# tracker.net
KiCad netlist of a schematic drawn in EAGLE
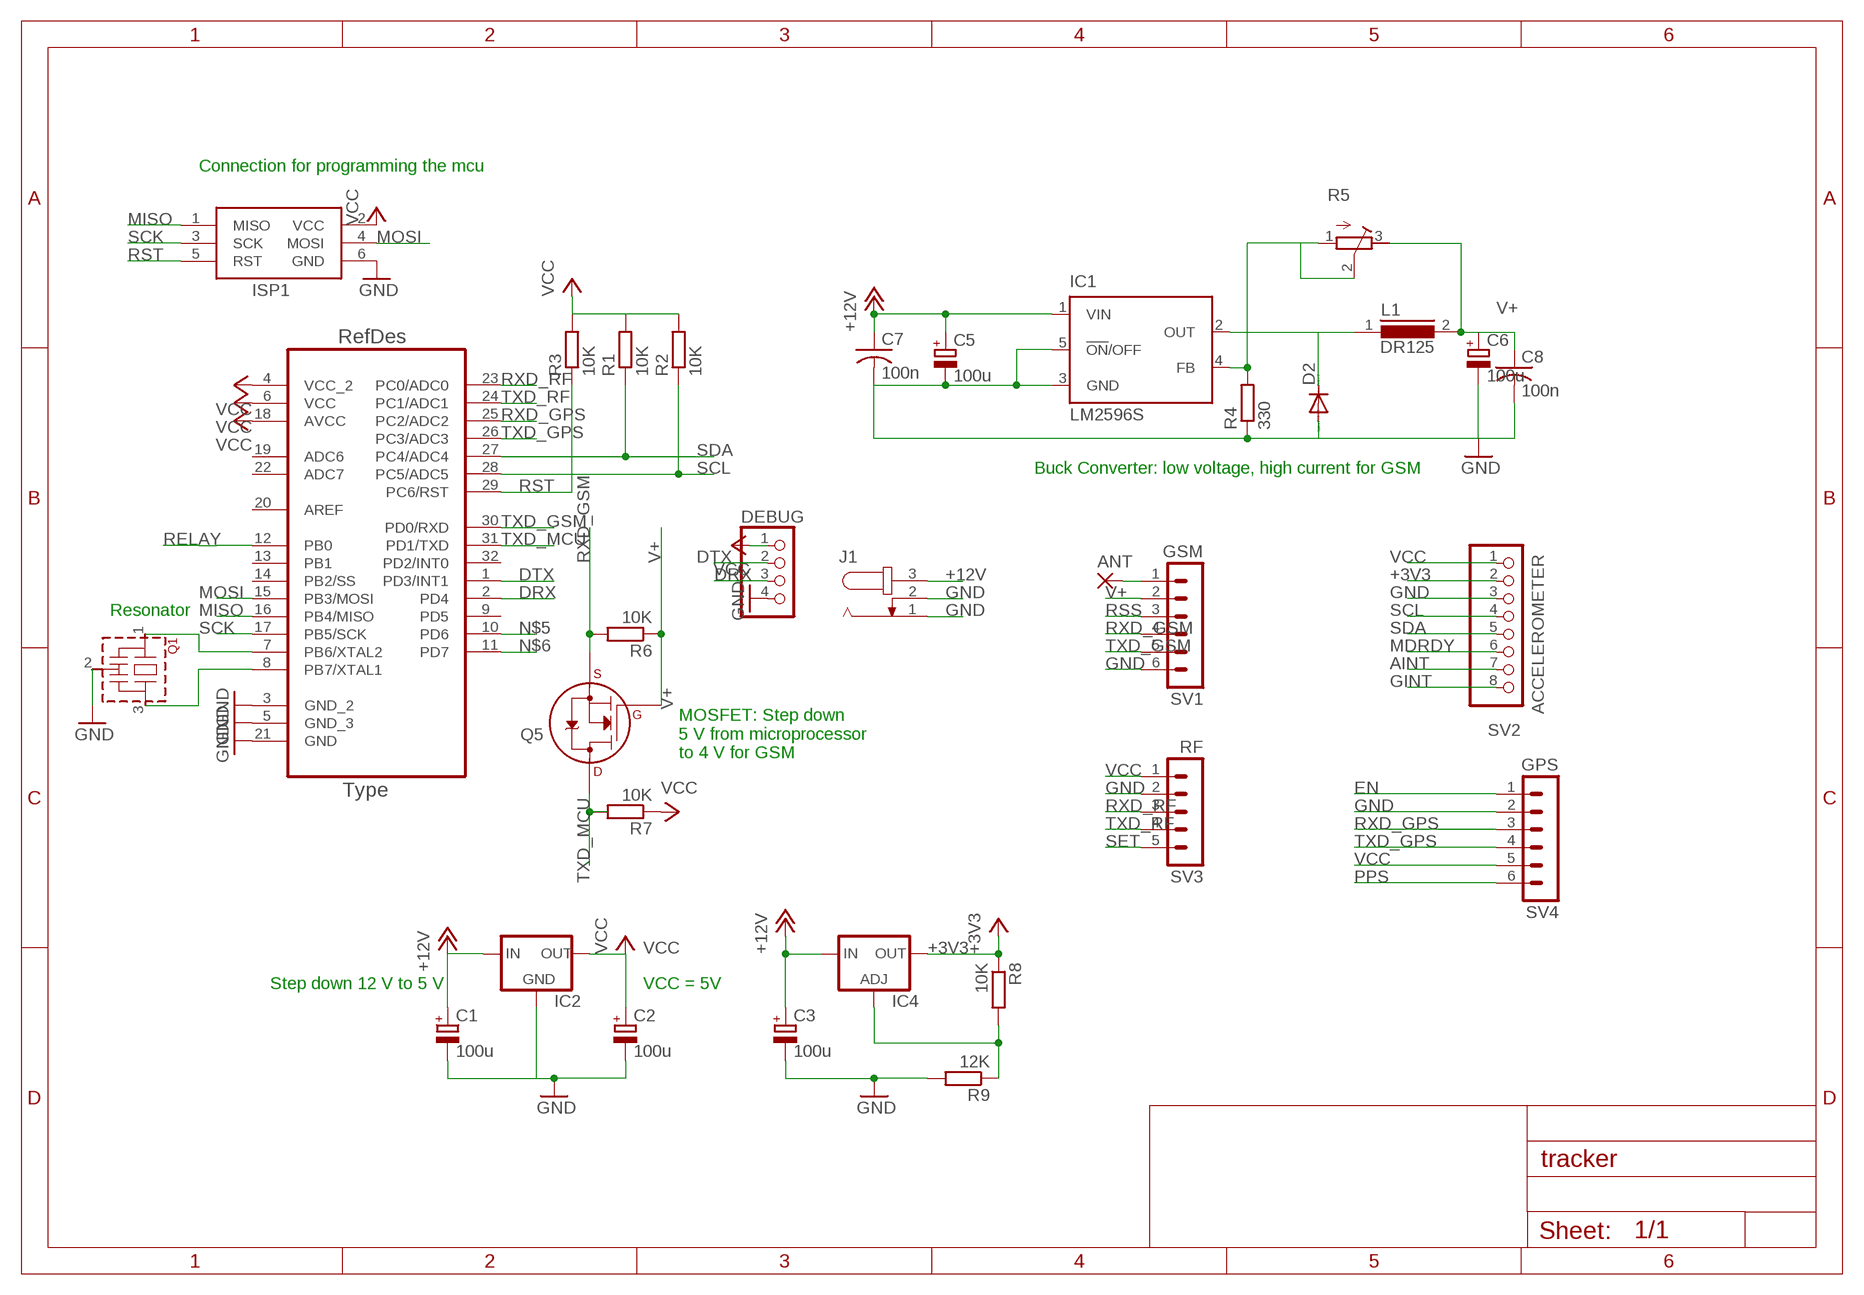
[diagram p0: schematic, sheet 1]

(export (version "E")
  (design (tool "Eeschema 10.0.6"))
  (components
    (comp (ref "ANT")
      (value "WIREPAD2,15/1,0")
      (footprint "eagle-import:2,15_1,0")
      (libsource (lib "eagle-import") (part "WIREPAD2,15/1,0"))
    )
    (comp (ref "C1")
      (value "100u")
      (footprint "eagle-import:E2,5-5")
      (libsource (lib "eagle-import") (part "CPOL-EUE2.5-5"))
    )
    (comp (ref "C2")
      (value "100u")
      (footprint "eagle-import:E2,5-5")
      (libsource (lib "eagle-import") (part "CPOL-EUE2.5-5"))
    )
    (comp (ref "C3")
      (value "100u")
      (footprint "eagle-import:E2,5-5")
      (libsource (lib "eagle-import") (part "CPOL-EUE2.5-5"))
    )
    (comp (ref "C5")
      (value "100u")
      (footprint "eagle-import:E2,5-5")
      (libsource (lib "eagle-import") (part "CPOL-EUE2.5-5"))
    )
    (comp (ref "C6")
      (value "100u")
      (footprint "eagle-import:E2,5-5")
      (libsource (lib "eagle-import") (part "CPOL-EUE2.5-5"))
    )
    (comp (ref "C7")
      (value "100n")
      (footprint "eagle-import:C025-024X044")
      (libsource (lib "eagle-import") (part "C-US025-024X044"))
    )
    (comp (ref "C8")
      (value "100n")
      (footprint "eagle-import:C025-024X044")
      (libsource (lib "eagle-import") (part "C-US025-024X044"))
    )
    (comp (ref "D2")
      (value "DIODE-DO-214AC")
      (footprint "eagle-import:DO-214AC")
      (libsource (lib "eagle-import") (part "DIODE-DO-214AC"))
    )
    (comp (ref "DEBUG")
      (value "PINHD-1X4")
      (footprint "eagle-import:1X04")
      (libsource (lib "eagle-import") (part "PINHD-1X4"))
    )
    (comp (ref "IC1")
      (value "LM2596S")
      (footprint "eagle-import:TO263-5")
      (fields (field (name "MF") "NATIONAL SEMICONDUCTOR") (field (name "MPN") "LM2596S-ADJ/NOPB"))
      (libsource (lib "eagle-import") (part "LM2596S"))
    )
    (comp (ref "IC2")
      (value "78XXS")
      (footprint "eagle-import:78XXS")
      (libsource (lib "eagle-import") (part "78XXS"))
    )
    (comp (ref "IC4")
      (value "LM317TS")
      (footprint "eagle-import:317TS")
      (libsource (lib "eagle-import") (part "LM317TS"))
    )
    (comp (ref "ISP1")
      (value "AVRISP-6")
      (footprint "eagle-import:AVRISP")
      (libsource (lib "eagle-import") (part "AVRISP-6"))
    )
    (comp (ref "J1")
      (value "JACK-PLUG0")
      (footprint "eagle-import:SPC4077")
      (libsource (lib "eagle-import") (part "JACK-PLUG0"))
    )
    (comp (ref "L1")
      (value "DR125")
      (footprint "eagle-import:DR125")
      (libsource (lib "eagle-import") (part "DR125"))
    )
    (comp (ref "Q1")
      (value "CSTLS_X")
      (footprint "eagle-import:CSTLS_X")
      (libsource (lib "eagle-import") (part "CSTLS_X"))
    )
    (comp (ref "Q5")
      (value "2N7000_TO92")
      (footprint "eagle-import:TO-92")
      (libsource (lib "eagle-import") (part "2N700_TO920"))
    )
    (comp (ref "R1")
      (value "10K")
      (footprint "eagle-import:R1210")
      (libsource (lib "eagle-import") (part "R-EU_R1210"))
    )
    (comp (ref "R2")
      (value "10K")
      (footprint "eagle-import:R1210")
      (libsource (lib "eagle-import") (part "R-EU_R1210"))
    )
    (comp (ref "R3")
      (value "10K")
      (footprint "eagle-import:R1210")
      (libsource (lib "eagle-import") (part "R-EU_R1210"))
    )
    (comp (ref "R4")
      (value "330")
      (footprint "eagle-import:R1210")
      (libsource (lib "eagle-import") (part "R-EU_R1210"))
    )
    (comp (ref "R5")
      (value "R-TRIMM64X")
      (footprint "eagle-import:RTRIM64X")
      (libsource (lib "eagle-import") (part "R-TRIMM64X"))
    )
    (comp (ref "R6")
      (value "10K")
      (footprint "eagle-import:R1210")
      (libsource (lib "eagle-import") (part "R-EU_R1210"))
    )
    (comp (ref "R7")
      (value "10K")
      (footprint "eagle-import:R1210")
      (libsource (lib "eagle-import") (part "R-EU_R1210"))
    )
    (comp (ref "R8")
      (value "10K")
      (footprint "eagle-import:0207_10")
      (libsource (lib "eagle-import") (part "resistor_348_R-EU_0207/10"))
    )
    (comp (ref "R9")
      (value "12K")
      (footprint "eagle-import:0207_10")
      (libsource (lib "eagle-import") (part "R-EU_0207/10"))
    )
    (comp (ref "SV1")
      (value "GSM")
      (footprint "eagle-import:MA06-1")
      (libsource (lib "eagle-import") (part "MA06-1"))
    )
    (comp (ref "SV2")
      (value "ACCELEROMETER")
      (footprint "eagle-import:1X08")
      (libsource (lib "eagle-import") (part "PINHD-1X8"))
    )
    (comp (ref "SV3")
      (value "RF")
      (footprint "eagle-import:MA05-1")
      (libsource (lib "eagle-import") (part "MA05-1"))
    )
    (comp (ref "SV4")
      (value "GPS")
      (footprint "eagle-import:MA06-1")
      (libsource (lib "eagle-import") (part "MA06-1"))
    )
    (comp (ref "U1")
      (value "ATMEGA328P-AU")
      (footprint "eagle-import:QFP80P900X900X120-32N")
      (libsource (lib "eagle-import") (part "ATMEGA328P-AU"))
    )
  )
  (nets
    (net (code "1") (name "+3V3") (class "Default")
      (node (ref "IC4") (pin "2") (pinfunction "OUT_2") (pintype "passive"))
      (node (ref "R8") (pin "1") (pinfunction "1_1") (pintype "passive"))
      (node (ref "SV2") (pin "2") (pinfunction "2_2") (pintype "passive"))
    )
    (net (code "2") (name "+12V") (class "Default")
      (node (ref "C1") (pin "+") (pinfunction "+_+") (pintype "passive"))
      (node (ref "C3") (pin "+") (pinfunction "+_+") (pintype "passive"))
      (node (ref "C5") (pin "+") (pinfunction "+_+") (pintype "passive"))
      (node (ref "C7") (pin "1") (pinfunction "1_1") (pintype "passive"))
      (node (ref "IC1") (pin "1") (pinfunction "VIN_1") (pintype "input"))
      (node (ref "IC2") (pin "IN") (pinfunction "IN_IN") (pintype "input"))
      (node (ref "IC4") (pin "3") (pinfunction "IN_3") (pintype "input"))
      (node (ref "J1") (pin "3") (pinfunction "3_3") (pintype "passive"))
    )
    (net (code "3") (name "/AINT") (class "Default")
      (node (ref "SV2") (pin "7") (pinfunction "7_7") (pintype "passive"))
    )
    (net (code "4") (name "/DRX") (class "Default")
      (node (ref "DEBUG") (pin "3") (pinfunction "3_3") (pintype "passive"))
      (node (ref "U1") (pin "2") (pinfunction "PD4_2") (pintype "bidirectional"))
    )
    (net (code "5") (name "/DTX") (class "Default")
      (node (ref "DEBUG") (pin "2") (pinfunction "2_2") (pintype "passive"))
      (node (ref "U1") (pin "1") (pinfunction "PD3/INT1_1") (pintype "bidirectional"))
    )
    (net (code "6") (name "/EN") (class "Default")
      (node (ref "SV4") (pin "1") (pinfunction "1_1") (pintype "passive"))
    )
    (net (code "7") (name "/GINT") (class "Default")
      (node (ref "SV2") (pin "8") (pinfunction "8_8") (pintype "passive"))
    )
    (net (code "8") (name "/MDRDY") (class "Default")
      (node (ref "SV2") (pin "6") (pinfunction "6_6") (pintype "passive"))
    )
    (net (code "9") (name "/MISO") (class "Default")
      (node (ref "ISP1") (pin "1") (pinfunction "MISO_1") (pintype "input"))
      (node (ref "U1") (pin "16") (pinfunction "PB4/MISO_16") (pintype "bidirectional"))
    )
    (net (code "10") (name "/MOSI") (class "Default")
      (node (ref "ISP1") (pin "4") (pinfunction "MOSI_4") (pintype "output"))
      (node (ref "U1") (pin "15") (pinfunction "PB3/MOSI_15") (pintype "bidirectional"))
    )
    (net (code "11") (name "/N$5") (class "Default")
      (node (ref "U1") (pin "10") (pinfunction "PD6_10") (pintype "bidirectional"))
    )
    (net (code "12") (name "/N$6") (class "Default")
      (node (ref "U1") (pin "11") (pinfunction "PD7_11") (pintype "bidirectional"))
    )
    (net (code "13") (name "/PPS") (class "Default")
      (node (ref "SV4") (pin "6") (pinfunction "6_6") (pintype "passive"))
    )
    (net (code "14") (name "/RELAY") (class "Default")
      (node (ref "U1") (pin "12") (pinfunction "PB0_12") (pintype "bidirectional"))
    )
    (net (code "15") (name "/RSS") (class "Default")
      (node (ref "SV1") (pin "3") (pinfunction "3_3") (pintype "passive"))
    )
    (net (code "16") (name "/RST") (class "Default")
      (node (ref "ISP1") (pin "5") (pinfunction "RST_5") (pintype "output"))
      (node (ref "R3") (pin "1") (pinfunction "1_1") (pintype "passive"))
      (node (ref "U1") (pin "29") (pinfunction "PC6/RST_29") (pintype "bidirectional"))
    )
    (net (code "17") (name "/RXD_GPS") (class "Default")
      (node (ref "SV4") (pin "3") (pinfunction "3_3") (pintype "passive"))
      (node (ref "U1") (pin "25") (pinfunction "PC2/ADC2_25") (pintype "bidirectional"))
    )
    (net (code "18") (name "/RXD_GSM") (class "Default")
      (node (ref "Q5") (pin "1") (pinfunction "S_1") (pintype "bidirectional"))
      (node (ref "R6") (pin "2") (pinfunction "2_2") (pintype "passive"))
      (node (ref "SV1") (pin "4") (pinfunction "4_4") (pintype "passive"))
    )
    (net (code "19") (name "/RXD_RF") (class "Default")
      (node (ref "SV3") (pin "3") (pinfunction "3_3") (pintype "passive"))
      (node (ref "U1") (pin "23") (pinfunction "PC0/ADC0_23") (pintype "bidirectional"))
    )
    (net (code "20") (name "/SCK") (class "Default")
      (node (ref "ISP1") (pin "3") (pinfunction "SCK_3") (pintype "output"))
      (node (ref "U1") (pin "17") (pinfunction "PB5/SCK_17") (pintype "bidirectional"))
    )
    (net (code "21") (name "/SCL") (class "Default")
      (node (ref "R2") (pin "1") (pinfunction "1_1") (pintype "passive"))
      (node (ref "SV2") (pin "4") (pinfunction "4_4") (pintype "passive"))
      (node (ref "U1") (pin "28") (pinfunction "PC5/ADC5_28") (pintype "bidirectional"))
    )
    (net (code "22") (name "/SDA") (class "Default")
      (node (ref "R1") (pin "1") (pinfunction "1_1") (pintype "passive"))
      (node (ref "SV2") (pin "5") (pinfunction "5_5") (pintype "passive"))
      (node (ref "U1") (pin "27") (pinfunction "PC4/ADC4_27") (pintype "bidirectional"))
    )
    (net (code "23") (name "/SET") (class "Default")
      (node (ref "SV3") (pin "5") (pinfunction "5_5") (pintype "passive"))
    )
    (net (code "24") (name "/TXD_GPS") (class "Default")
      (node (ref "SV4") (pin "4") (pinfunction "4_4") (pintype "passive"))
      (node (ref "U1") (pin "26") (pinfunction "PC3/ADC3_26") (pintype "bidirectional"))
    )
    (net (code "25") (name "/TXD_GSM") (class "Default")
      (node (ref "SV1") (pin "5") (pinfunction "5_5") (pintype "passive"))
      (node (ref "U1") (pin "30") (pinfunction "PD0/RXD_30") (pintype "bidirectional"))
    )
    (net (code "26") (name "/TXD_MCU") (class "Default")
      (node (ref "Q5") (pin "3") (pinfunction "D_3") (pintype "bidirectional"))
      (node (ref "R7") (pin "2") (pinfunction "2_2") (pintype "passive"))
      (node (ref "U1") (pin "31") (pinfunction "PD1/TXD_31") (pintype "bidirectional"))
    )
    (net (code "27") (name "/TXD_RF") (class "Default")
      (node (ref "SV3") (pin "4") (pinfunction "4_4") (pintype "passive"))
      (node (ref "U1") (pin "24") (pinfunction "PC1/ADC1_24") (pintype "bidirectional"))
    )
    (net (code "28") (name "/V+") (class "Default")
      (node (ref "C6") (pin "+") (pinfunction "+_+") (pintype "passive"))
      (node (ref "C8") (pin "1") (pinfunction "1_1") (pintype "passive"))
      (node (ref "L1") (pin "2") (pinfunction "2_2") (pintype "passive"))
      (node (ref "Q5") (pin "2") (pinfunction "G_2") (pintype "tri_state"))
      (node (ref "R5") (pin "3") (pinfunction "E_3") (pintype "passive"))
      (node (ref "R6") (pin "1") (pinfunction "1_1") (pintype "passive"))
      (node (ref "SV1") (pin "2") (pinfunction "2_2") (pintype "passive"))
    )
    (net (code "29") (name "GND") (class "Default")
      (node (ref "C1") (pin "-") (pinfunction "-_-") (pintype "passive"))
      (node (ref "C2") (pin "-") (pinfunction "-_-") (pintype "passive"))
      (node (ref "C3") (pin "-") (pinfunction "-_-") (pintype "passive"))
      (node (ref "C5") (pin "-") (pinfunction "-_-") (pintype "passive"))
      (node (ref "C6") (pin "-") (pinfunction "-_-") (pintype "passive"))
      (node (ref "C7") (pin "2") (pinfunction "2_2") (pintype "passive"))
      (node (ref "C8") (pin "2") (pinfunction "2_2") (pintype "passive"))
      (node (ref "D2") (pin "A") (pinfunction "A_A") (pintype "passive"))
      (node (ref "DEBUG") (pin "4") (pinfunction "4_4") (pintype "passive"))
      (node (ref "IC1") (pin "3") (pinfunction "GND_3") (pintype "power_in"))
      (node (ref "IC1") (pin "5") (pinfunction "~{ON}/OFF_5") (pintype "input"))
      (node (ref "IC2") (pin "GND") (pinfunction "GND_GND") (pintype "input"))
      (node (ref "ISP1") (pin "6") (pinfunction "GND_6") (pintype "power_in"))
      (node (ref "J1") (pin "1") (pinfunction "1_1") (pintype "passive"))
      (node (ref "J1") (pin "2") (pinfunction "2_2") (pintype "passive"))
      (node (ref "Q1") (pin "2") (pinfunction "VSS_2") (pintype "power_in"))
      (node (ref "R4") (pin "1") (pinfunction "1_1") (pintype "passive"))
      (node (ref "R9") (pin "2") (pinfunction "2_2") (pintype "passive"))
      (node (ref "SV1") (pin "6") (pinfunction "6_6") (pintype "passive"))
      (node (ref "SV2") (pin "3") (pinfunction "3_3") (pintype "passive"))
      (node (ref "SV3") (pin "2") (pinfunction "2_2") (pintype "passive"))
      (node (ref "SV4") (pin "2") (pinfunction "2_2") (pintype "passive"))
      (node (ref "U1") (pin "21") (pinfunction "GND_21") (pintype "passive"))
      (node (ref "U1") (pin "3") (pinfunction "GND_2_3") (pintype "passive"))
      (node (ref "U1") (pin "5") (pinfunction "GND_3_5") (pintype "passive"))
    )
    (net (code "30") (name "Net-(ANT-P)") (class "Default")
      (node (ref "ANT") (pin "1") (pinfunction "P_1") (pintype "passive"))
      (node (ref "SV1") (pin "1") (pinfunction "1_1") (pintype "passive"))
    )
    (net (code "31") (name "Net-(IC1-FB)") (class "Default")
      (node (ref "IC1") (pin "4") (pinfunction "FB_4") (pintype "input"))
      (node (ref "R4") (pin "2") (pinfunction "2_2") (pintype "passive"))
      (node (ref "R5") (pin "1") (pinfunction "A_1") (pintype "passive"))
      (node (ref "R5") (pin "2") (pinfunction "S_2") (pintype "passive"))
    )
    (net (code "32") (name "Net-(IC1-OUT)") (class "Default")
      (node (ref "D2") (pin "C") (pinfunction "C_C") (pintype "passive"))
      (node (ref "IC1") (pin "2") (pinfunction "OUT_2") (pintype "output"))
      (node (ref "L1") (pin "1") (pinfunction "1_1") (pintype "passive"))
    )
    (net (code "33") (name "Net-(IC4-ADJ)") (class "Default")
      (node (ref "IC4") (pin "1") (pinfunction "ADJ_1") (pintype "input"))
      (node (ref "R8") (pin "2") (pinfunction "2_2") (pintype "passive"))
      (node (ref "R9") (pin "1") (pinfunction "1_1") (pintype "passive"))
    )
    (net (code "34") (name "Net-(U1-PB6{slash}XTAL2)") (class "Default")
      (node (ref "Q1") (pin "1") (pinfunction "1_1") (pintype "output"))
      (node (ref "U1") (pin "7") (pinfunction "PB6/XTAL2_7") (pintype "bidirectional"))
    )
    (net (code "35") (name "Net-(U1-PB7{slash}XTAL1)") (class "Default")
      (node (ref "Q1") (pin "3") (pinfunction "3_3") (pintype "input"))
      (node (ref "U1") (pin "8") (pinfunction "PB7/XTAL1_8") (pintype "bidirectional"))
    )
    (net (code "36") (name "VCC") (class "Default")
      (node (ref "C2") (pin "+") (pinfunction "+_+") (pintype "passive"))
      (node (ref "DEBUG") (pin "1") (pinfunction "1_1") (pintype "passive"))
      (node (ref "IC2") (pin "OUT") (pinfunction "OUT_OUT") (pintype "passive"))
      (node (ref "ISP1") (pin "2") (pinfunction "VCC_2") (pintype "power_in"))
      (node (ref "R1") (pin "2") (pinfunction "2_2") (pintype "passive"))
      (node (ref "R2") (pin "2") (pinfunction "2_2") (pintype "passive"))
      (node (ref "R3") (pin "2") (pinfunction "2_2") (pintype "passive"))
      (node (ref "R7") (pin "1") (pinfunction "1_1") (pintype "passive"))
      (node (ref "SV2") (pin "1") (pinfunction "1_1") (pintype "passive"))
      (node (ref "SV3") (pin "1") (pinfunction "1_1") (pintype "passive"))
      (node (ref "SV4") (pin "5") (pinfunction "5_5") (pintype "passive"))
      (node (ref "U1") (pin "18") (pinfunction "AVCC_18") (pintype "power_in"))
      (node (ref "U1") (pin "4") (pinfunction "VCC_2_4") (pintype "power_in"))
      (node (ref "U1") (pin "6") (pinfunction "VCC_6") (pintype "power_in"))
    )
    (net (code "37") (name "unconnected-(U1-ADC6-Pad19)") (class "Default")
      (node (ref "U1") (pin "19") (pinfunction "ADC6_19") (pintype "input"))
    )
    (net (code "38") (name "unconnected-(U1-ADC7-Pad22)") (class "Default")
      (node (ref "U1") (pin "22") (pinfunction "ADC7_22") (pintype "input"))
    )
    (net (code "39") (name "unconnected-(U1-AREF-Pad20)") (class "Default")
      (node (ref "U1") (pin "20") (pinfunction "AREF_20") (pintype "input"))
    )
    (net (code "40") (name "unconnected-(U1-PB1-Pad13)") (class "Default")
      (node (ref "U1") (pin "13") (pinfunction "PB1_13") (pintype "bidirectional"))
    )
    (net (code "41") (name "unconnected-(U1-PB2{slash}SS-Pad14)") (class "Default")
      (node (ref "U1") (pin "14") (pinfunction "PB2/SS_14") (pintype "bidirectional"))
    )
    (net (code "42") (name "unconnected-(U1-PD2{slash}INT0-Pad32)") (class "Default")
      (node (ref "U1") (pin "32") (pinfunction "PD2/INT0_32") (pintype "bidirectional"))
    )
    (net (code "43") (name "unconnected-(U1-PD5-Pad9)") (class "Default")
      (node (ref "U1") (pin "9") (pinfunction "PD5_9") (pintype "bidirectional"))
    )
  )
)
